# backplane2.net
KiCad netlist of a schematic drawn in EAGLE
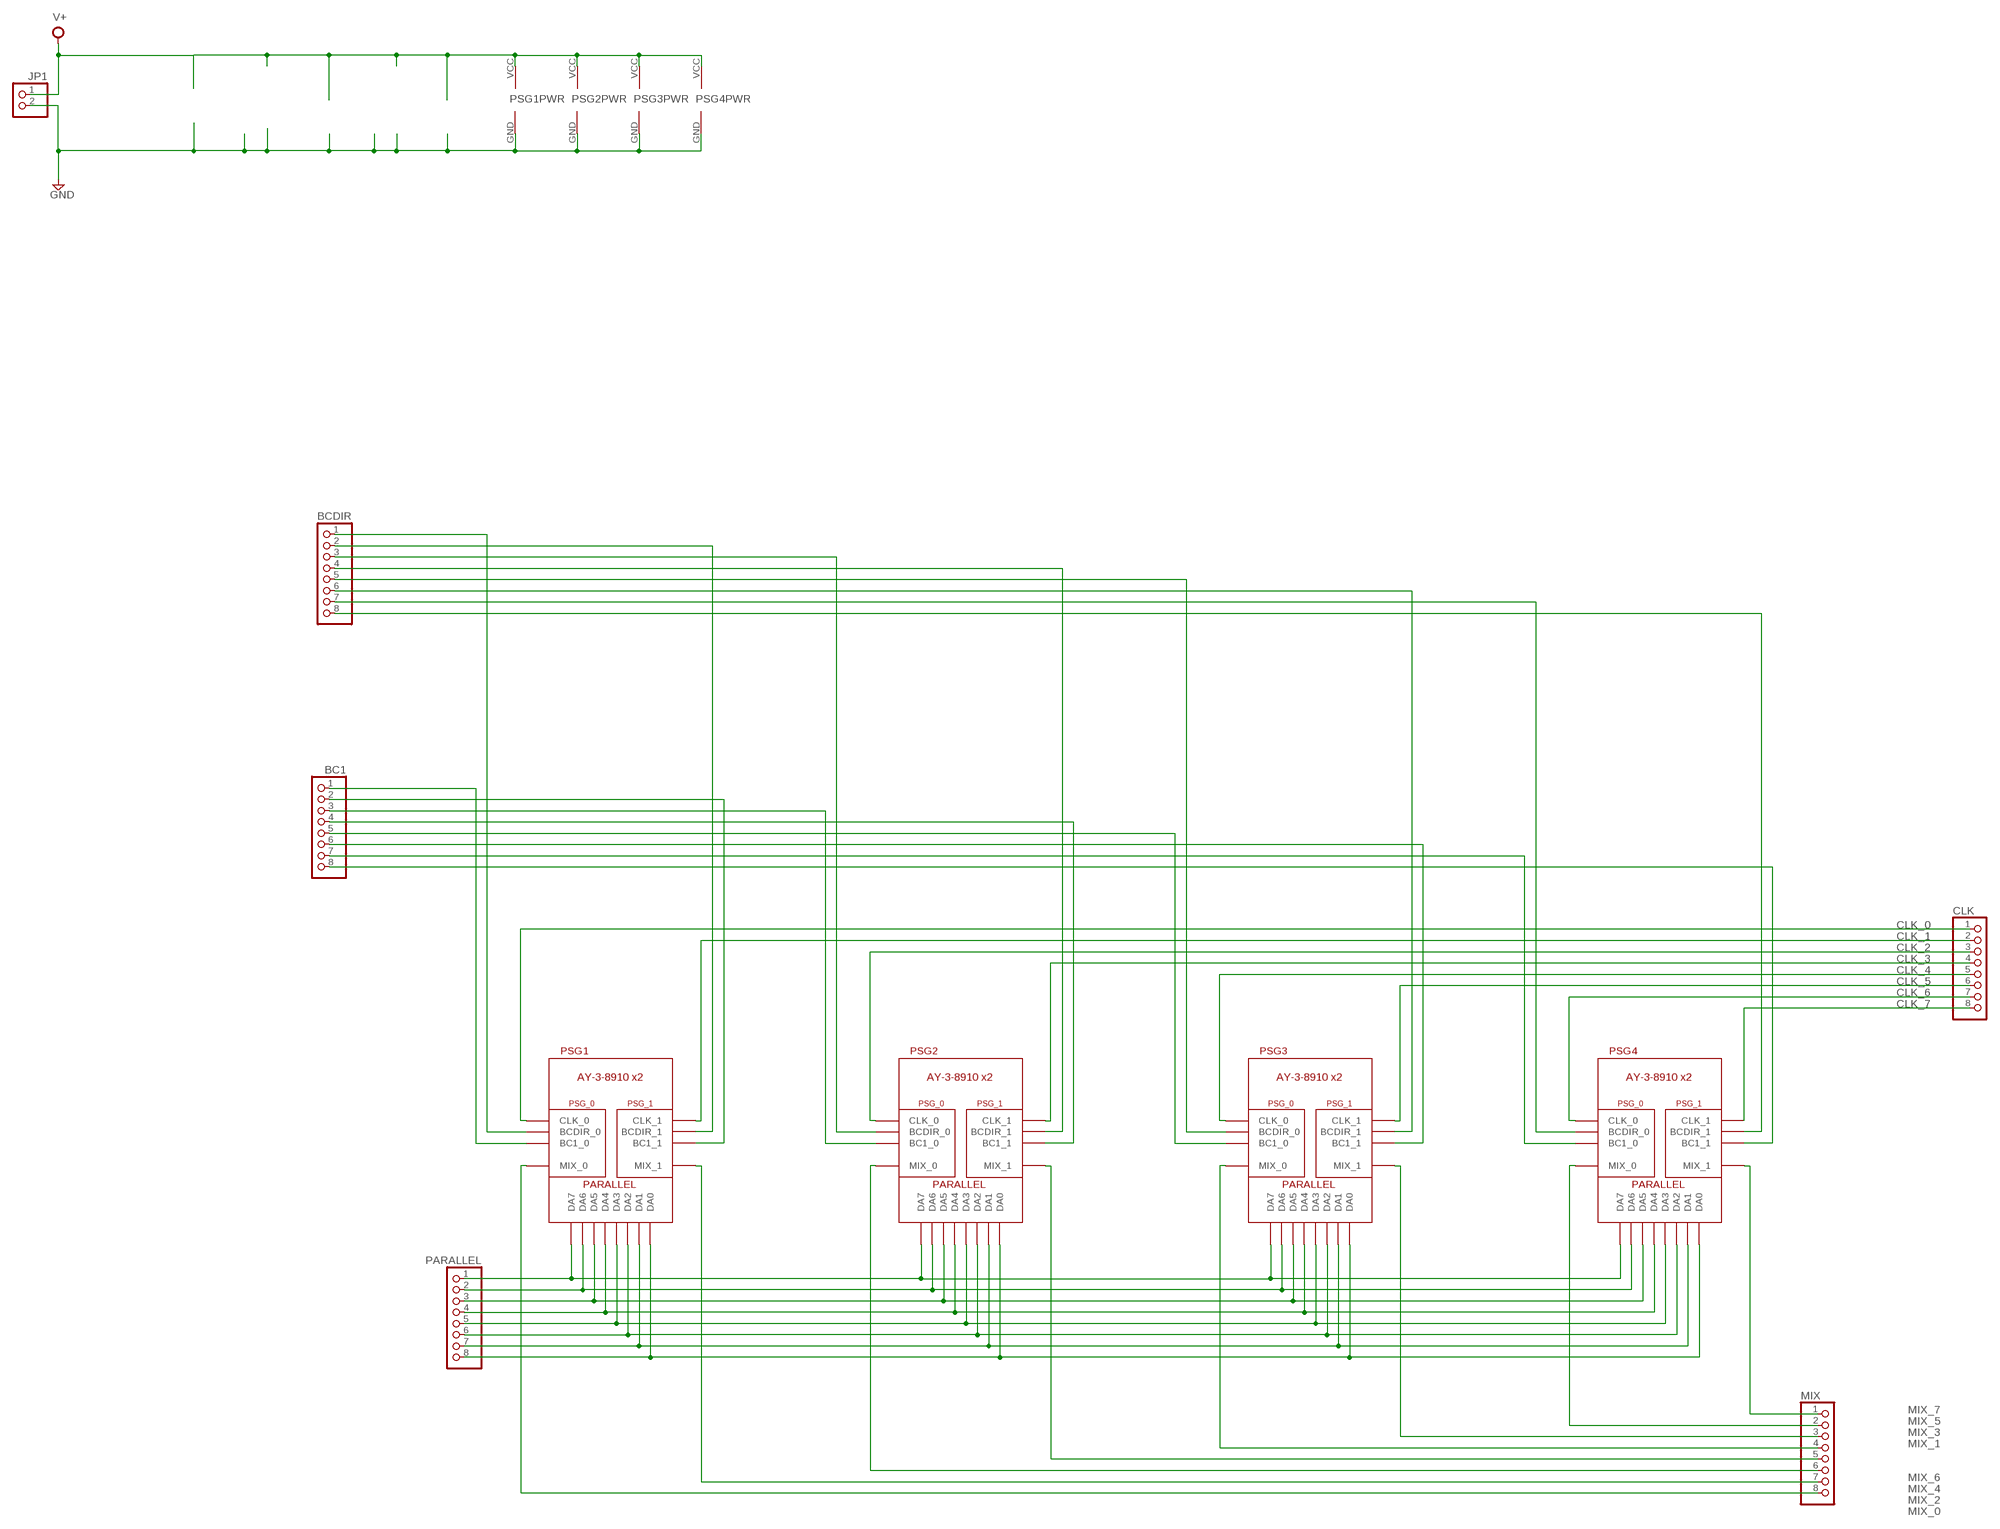
[diagram p0: schematic, sheet 1]

(export (version "E")
  (design (tool "Eeschema 10.0.6"))
  (components
    (comp (ref "BC1")
      (value "PINHD-1X8")
      (footprint "eagle-import:1X08")
      (libsource (lib "eagle-import") (part "PINHD-1X8"))
    )
    (comp (ref "BCDIR")
      (value "PINHD-1X8")
      (footprint "eagle-import:1X08")
      (libsource (lib "eagle-import") (part "PINHD-1X8"))
    )
    (comp (ref "CLK")
      (value "PINHD-1X8")
      (footprint "eagle-import:1X08")
      (libsource (lib "eagle-import") (part "PINHD-1X8"))
    )
    (comp (ref "JP1")
      (value "PINHD-1X2")
      (footprint "eagle-import:1X02")
      (libsource (lib "eagle-import") (part "PINHD-1X2"))
    )
    (comp (ref "MIX")
      (value "PINHD-1X8")
      (footprint "eagle-import:1X08")
      (libsource (lib "eagle-import") (part "PINHD-1X8"))
    )
    (comp (ref "PARALLEL")
      (value "PINHD-1X8")
      (footprint "eagle-import:1X08")
      (libsource (lib "eagle-import") (part "PINHD-1X8"))
    )
    (comp (ref "PSG1")
      (value "DUAL_PSG_DAUGHTER")
      (footprint "eagle-import:DUAL_PSG_DAUGHTER")
      (libsource (lib "eagle-import") (part "DUAL_PSG_DAUGHTER"))
    )
    (comp (ref "PSG2")
      (value "DUAL_PSG_DAUGHTER")
      (footprint "eagle-import:DUAL_PSG_DAUGHTER")
      (libsource (lib "eagle-import") (part "DUAL_PSG_DAUGHTER"))
    )
    (comp (ref "PSG3")
      (value "DUAL_PSG_DAUGHTER")
      (footprint "eagle-import:DUAL_PSG_DAUGHTER")
      (libsource (lib "eagle-import") (part "DUAL_PSG_DAUGHTER"))
    )
    (comp (ref "PSG4")
      (value "DUAL_PSG_DAUGHTER")
      (footprint "eagle-import:DUAL_PSG_DAUGHTER")
      (libsource (lib "eagle-import") (part "DUAL_PSG_DAUGHTER"))
    )
  )
  (nets
    (net (code "1") (name "/CLK_0") (class "Default")
      (node (ref "CLK") (pin "1") (pinfunction "1_1") (pintype "passive"))
      (node (ref "PSG1") (pin "CLK_0") (pinfunction "CLK_0_CLK_0") (pintype "input"))
    )
    (net (code "2") (name "/CLK_1") (class "Default")
      (node (ref "CLK") (pin "2") (pinfunction "2_2") (pintype "passive"))
      (node (ref "PSG1") (pin "CLK_1") (pinfunction "CLK_1_CLK_1") (pintype "input"))
    )
    (net (code "3") (name "/CLK_2") (class "Default")
      (node (ref "CLK") (pin "3") (pinfunction "3_3") (pintype "passive"))
      (node (ref "PSG2") (pin "CLK_0") (pinfunction "CLK_0_CLK_0") (pintype "input"))
    )
    (net (code "4") (name "/CLK_3") (class "Default")
      (node (ref "CLK") (pin "4") (pinfunction "4_4") (pintype "passive"))
      (node (ref "PSG2") (pin "CLK_1") (pinfunction "CLK_1_CLK_1") (pintype "input"))
    )
    (net (code "5") (name "/CLK_4") (class "Default")
      (node (ref "CLK") (pin "5") (pinfunction "5_5") (pintype "passive"))
      (node (ref "PSG3") (pin "CLK_0") (pinfunction "CLK_0_CLK_0") (pintype "input"))
    )
    (net (code "6") (name "/CLK_5") (class "Default")
      (node (ref "CLK") (pin "6") (pinfunction "6_6") (pintype "passive"))
      (node (ref "PSG3") (pin "CLK_1") (pinfunction "CLK_1_CLK_1") (pintype "input"))
    )
    (net (code "7") (name "/CLK_6") (class "Default")
      (node (ref "CLK") (pin "7") (pinfunction "7_7") (pintype "passive"))
      (node (ref "PSG4") (pin "CLK_0") (pinfunction "CLK_0_CLK_0") (pintype "input"))
    )
    (net (code "8") (name "/CLK_7") (class "Default")
      (node (ref "CLK") (pin "8") (pinfunction "8_8") (pintype "passive"))
      (node (ref "PSG4") (pin "CLK_1") (pinfunction "CLK_1_CLK_1") (pintype "input"))
    )
    (net (code "9") (name "/MIX_0") (class "Default")
      (node (ref "MIX") (pin "8") (pinfunction "8_8") (pintype "passive"))
      (node (ref "PSG1") (pin "MIX_0") (pinfunction "MIX_0_MIX_0") (pintype "output"))
    )
    (net (code "10") (name "/MIX_1") (class "Default")
      (node (ref "MIX") (pin "7") (pinfunction "7_7") (pintype "passive"))
      (node (ref "PSG1") (pin "MIX_1") (pinfunction "MIX_1_MIX_1") (pintype "output"))
    )
    (net (code "11") (name "/MIX_2") (class "Default")
      (node (ref "MIX") (pin "6") (pinfunction "6_6") (pintype "passive"))
      (node (ref "PSG2") (pin "MIX_0") (pinfunction "MIX_0_MIX_0") (pintype "output"))
    )
    (net (code "12") (name "/MIX_3") (class "Default")
      (node (ref "MIX") (pin "5") (pinfunction "5_5") (pintype "passive"))
      (node (ref "PSG2") (pin "MIX_1") (pinfunction "MIX_1_MIX_1") (pintype "output"))
    )
    (net (code "13") (name "/MIX_4") (class "Default")
      (node (ref "MIX") (pin "4") (pinfunction "4_4") (pintype "passive"))
      (node (ref "PSG3") (pin "MIX_0") (pinfunction "MIX_0_MIX_0") (pintype "output"))
    )
    (net (code "14") (name "/MIX_5") (class "Default")
      (node (ref "MIX") (pin "3") (pinfunction "3_3") (pintype "passive"))
      (node (ref "PSG3") (pin "MIX_1") (pinfunction "MIX_1_MIX_1") (pintype "output"))
    )
    (net (code "15") (name "/MIX_6") (class "Default")
      (node (ref "MIX") (pin "2") (pinfunction "2_2") (pintype "passive"))
      (node (ref "PSG4") (pin "MIX_0") (pinfunction "MIX_0_MIX_0") (pintype "output"))
    )
    (net (code "16") (name "/MIX_7") (class "Default")
      (node (ref "MIX") (pin "1") (pinfunction "1_1") (pintype "passive"))
      (node (ref "PSG4") (pin "MIX_1") (pinfunction "MIX_1_MIX_1") (pintype "output"))
    )
    (net (code "17") (name "GND") (class "Default")
      (node (ref "JP1") (pin "2") (pinfunction "2_2") (pintype "passive"))
      (node (ref "PSG1") (pin "GND") (pinfunction "GND_GND") (pintype "power_in"))
      (node (ref "PSG2") (pin "GND") (pinfunction "GND_GND") (pintype "power_in"))
      (node (ref "PSG3") (pin "GND") (pinfunction "GND_GND") (pintype "power_in"))
      (node (ref "PSG4") (pin "GND") (pinfunction "GND_GND") (pintype "power_in"))
    )
    (net (code "18") (name "Net-(BC1-Pad1)") (class "Default")
      (node (ref "BC1") (pin "1") (pinfunction "1_1") (pintype "passive"))
      (node (ref "PSG1") (pin "BC1_0") (pinfunction "BC1_0_BC1_0") (pintype "input"))
    )
    (net (code "19") (name "Net-(BC1-Pad2)") (class "Default")
      (node (ref "BC1") (pin "2") (pinfunction "2_2") (pintype "passive"))
      (node (ref "PSG1") (pin "BC1_1") (pinfunction "BC1_1_BC1_1") (pintype "input"))
    )
    (net (code "20") (name "Net-(BC1-Pad3)") (class "Default")
      (node (ref "BC1") (pin "3") (pinfunction "3_3") (pintype "passive"))
      (node (ref "PSG2") (pin "BC1_0") (pinfunction "BC1_0_BC1_0") (pintype "input"))
    )
    (net (code "21") (name "Net-(BC1-Pad4)") (class "Default")
      (node (ref "BC1") (pin "4") (pinfunction "4_4") (pintype "passive"))
      (node (ref "PSG2") (pin "BC1_1") (pinfunction "BC1_1_BC1_1") (pintype "input"))
    )
    (net (code "22") (name "Net-(BC1-Pad5)") (class "Default")
      (node (ref "BC1") (pin "5") (pinfunction "5_5") (pintype "passive"))
      (node (ref "PSG3") (pin "BC1_0") (pinfunction "BC1_0_BC1_0") (pintype "input"))
    )
    (net (code "23") (name "Net-(BC1-Pad6)") (class "Default")
      (node (ref "BC1") (pin "6") (pinfunction "6_6") (pintype "passive"))
      (node (ref "PSG3") (pin "BC1_1") (pinfunction "BC1_1_BC1_1") (pintype "input"))
    )
    (net (code "24") (name "Net-(BC1-Pad7)") (class "Default")
      (node (ref "BC1") (pin "7") (pinfunction "7_7") (pintype "passive"))
      (node (ref "PSG4") (pin "BC1_0") (pinfunction "BC1_0_BC1_0") (pintype "input"))
    )
    (net (code "25") (name "Net-(BC1-Pad8)") (class "Default")
      (node (ref "BC1") (pin "8") (pinfunction "8_8") (pintype "passive"))
      (node (ref "PSG4") (pin "BC1_1") (pinfunction "BC1_1_BC1_1") (pintype "input"))
    )
    (net (code "26") (name "Net-(BCDIR-Pad1)") (class "Default")
      (node (ref "BCDIR") (pin "1") (pinfunction "1_1") (pintype "passive"))
      (node (ref "PSG1") (pin "BCDIR_0") (pinfunction "BCDIR_0_BCDIR_0") (pintype "input"))
    )
    (net (code "27") (name "Net-(BCDIR-Pad2)") (class "Default")
      (node (ref "BCDIR") (pin "2") (pinfunction "2_2") (pintype "passive"))
      (node (ref "PSG1") (pin "BCDIR_1") (pinfunction "BCDIR_1_BCDIR_1") (pintype "input"))
    )
    (net (code "28") (name "Net-(BCDIR-Pad3)") (class "Default")
      (node (ref "BCDIR") (pin "3") (pinfunction "3_3") (pintype "passive"))
      (node (ref "PSG2") (pin "BCDIR_0") (pinfunction "BCDIR_0_BCDIR_0") (pintype "input"))
    )
    (net (code "29") (name "Net-(BCDIR-Pad4)") (class "Default")
      (node (ref "BCDIR") (pin "4") (pinfunction "4_4") (pintype "passive"))
      (node (ref "PSG2") (pin "BCDIR_1") (pinfunction "BCDIR_1_BCDIR_1") (pintype "input"))
    )
    (net (code "30") (name "Net-(BCDIR-Pad5)") (class "Default")
      (node (ref "BCDIR") (pin "5") (pinfunction "5_5") (pintype "passive"))
      (node (ref "PSG3") (pin "BCDIR_0") (pinfunction "BCDIR_0_BCDIR_0") (pintype "input"))
    )
    (net (code "31") (name "Net-(BCDIR-Pad6)") (class "Default")
      (node (ref "BCDIR") (pin "6") (pinfunction "6_6") (pintype "passive"))
      (node (ref "PSG3") (pin "BCDIR_1") (pinfunction "BCDIR_1_BCDIR_1") (pintype "input"))
    )
    (net (code "32") (name "Net-(BCDIR-Pad7)") (class "Default")
      (node (ref "BCDIR") (pin "7") (pinfunction "7_7") (pintype "passive"))
      (node (ref "PSG4") (pin "BCDIR_0") (pinfunction "BCDIR_0_BCDIR_0") (pintype "input"))
    )
    (net (code "33") (name "Net-(BCDIR-Pad8)") (class "Default")
      (node (ref "BCDIR") (pin "8") (pinfunction "8_8") (pintype "passive"))
      (node (ref "PSG4") (pin "BCDIR_1") (pinfunction "BCDIR_1_BCDIR_1") (pintype "input"))
    )
    (net (code "34") (name "Net-(PARALLEL-Pad1)") (class "Default")
      (node (ref "PARALLEL") (pin "1") (pinfunction "1_1") (pintype "passive"))
      (node (ref "PSG1") (pin "DA7") (pinfunction "DA7_DA7") (pintype "bidirectional"))
      (node (ref "PSG2") (pin "DA7") (pinfunction "DA7_DA7") (pintype "bidirectional"))
      (node (ref "PSG3") (pin "DA7") (pinfunction "DA7_DA7") (pintype "bidirectional"))
      (node (ref "PSG4") (pin "DA7") (pinfunction "DA7_DA7") (pintype "bidirectional"))
    )
    (net (code "35") (name "Net-(PARALLEL-Pad2)") (class "Default")
      (node (ref "PARALLEL") (pin "2") (pinfunction "2_2") (pintype "passive"))
      (node (ref "PSG1") (pin "DA6") (pinfunction "DA6_DA6") (pintype "bidirectional"))
      (node (ref "PSG2") (pin "DA6") (pinfunction "DA6_DA6") (pintype "bidirectional"))
      (node (ref "PSG3") (pin "DA6") (pinfunction "DA6_DA6") (pintype "bidirectional"))
      (node (ref "PSG4") (pin "DA6") (pinfunction "DA6_DA6") (pintype "bidirectional"))
    )
    (net (code "36") (name "Net-(PARALLEL-Pad3)") (class "Default")
      (node (ref "PARALLEL") (pin "3") (pinfunction "3_3") (pintype "passive"))
      (node (ref "PSG1") (pin "DA5") (pinfunction "DA5_DA5") (pintype "bidirectional"))
      (node (ref "PSG2") (pin "DA5") (pinfunction "DA5_DA5") (pintype "bidirectional"))
      (node (ref "PSG3") (pin "DA5") (pinfunction "DA5_DA5") (pintype "bidirectional"))
      (node (ref "PSG4") (pin "DA5") (pinfunction "DA5_DA5") (pintype "bidirectional"))
    )
    (net (code "37") (name "Net-(PARALLEL-Pad4)") (class "Default")
      (node (ref "PARALLEL") (pin "4") (pinfunction "4_4") (pintype "passive"))
      (node (ref "PSG1") (pin "DA4") (pinfunction "DA4_DA4") (pintype "bidirectional"))
      (node (ref "PSG2") (pin "DA4") (pinfunction "DA4_DA4") (pintype "bidirectional"))
      (node (ref "PSG3") (pin "DA4") (pinfunction "DA4_DA4") (pintype "bidirectional"))
      (node (ref "PSG4") (pin "DA4") (pinfunction "DA4_DA4") (pintype "bidirectional"))
    )
    (net (code "38") (name "Net-(PARALLEL-Pad5)") (class "Default")
      (node (ref "PARALLEL") (pin "5") (pinfunction "5_5") (pintype "passive"))
      (node (ref "PSG1") (pin "DA3") (pinfunction "DA3_DA3") (pintype "bidirectional"))
      (node (ref "PSG2") (pin "DA3") (pinfunction "DA3_DA3") (pintype "bidirectional"))
      (node (ref "PSG3") (pin "DA3") (pinfunction "DA3_DA3") (pintype "bidirectional"))
      (node (ref "PSG4") (pin "DA3") (pinfunction "DA3_DA3") (pintype "bidirectional"))
    )
    (net (code "39") (name "Net-(PARALLEL-Pad6)") (class "Default")
      (node (ref "PARALLEL") (pin "6") (pinfunction "6_6") (pintype "passive"))
      (node (ref "PSG1") (pin "DA2") (pinfunction "DA2_DA2") (pintype "bidirectional"))
      (node (ref "PSG2") (pin "DA2") (pinfunction "DA2_DA2") (pintype "bidirectional"))
      (node (ref "PSG3") (pin "DA2") (pinfunction "DA2_DA2") (pintype "bidirectional"))
      (node (ref "PSG4") (pin "DA2") (pinfunction "DA2_DA2") (pintype "bidirectional"))
    )
    (net (code "40") (name "Net-(PARALLEL-Pad7)") (class "Default")
      (node (ref "PARALLEL") (pin "7") (pinfunction "7_7") (pintype "passive"))
      (node (ref "PSG1") (pin "DA1") (pinfunction "DA1_DA1") (pintype "bidirectional"))
      (node (ref "PSG2") (pin "DA1") (pinfunction "DA1_DA1") (pintype "bidirectional"))
      (node (ref "PSG3") (pin "DA1") (pinfunction "DA1_DA1") (pintype "bidirectional"))
      (node (ref "PSG4") (pin "DA1") (pinfunction "DA1_DA1") (pintype "bidirectional"))
    )
    (net (code "41") (name "Net-(PARALLEL-Pad8)") (class "Default")
      (node (ref "PARALLEL") (pin "8") (pinfunction "8_8") (pintype "passive"))
      (node (ref "PSG1") (pin "DA0") (pinfunction "DA0_DA0") (pintype "bidirectional"))
      (node (ref "PSG2") (pin "DA0") (pinfunction "DA0_DA0") (pintype "bidirectional"))
      (node (ref "PSG3") (pin "DA0") (pinfunction "DA0_DA0") (pintype "bidirectional"))
      (node (ref "PSG4") (pin "DA0") (pinfunction "DA0_DA0") (pintype "bidirectional"))
    )
    (net (code "42") (name "V+") (class "Default")
      (node (ref "JP1") (pin "1") (pinfunction "1_1") (pintype "passive"))
      (node (ref "PSG1") (pin "VCC") (pinfunction "VCC_VCC") (pintype "power_in"))
      (node (ref "PSG2") (pin "VCC") (pinfunction "VCC_VCC") (pintype "power_in"))
      (node (ref "PSG3") (pin "VCC") (pinfunction "VCC_VCC") (pintype "power_in"))
      (node (ref "PSG4") (pin "VCC") (pinfunction "VCC_VCC") (pintype "power_in"))
    )
  )
)
